# fonte.net
KiCad netlist of a schematic drawn in EAGLE
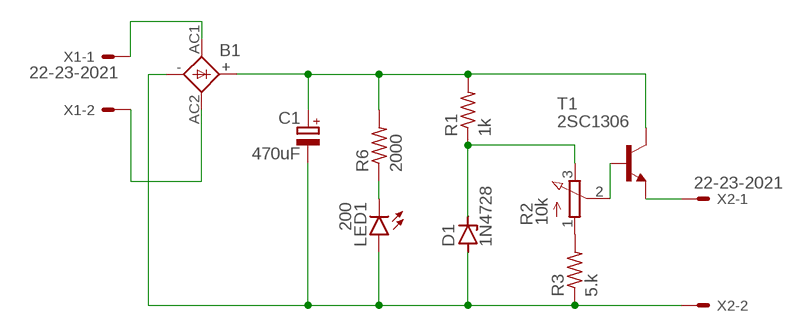
[diagram p0: schematic, sheet 1]

(export (version "E")
  (design (tool "Eeschema 10.0.6"))
  (components
    (comp (ref "B1")
      (value "GBPC1")
      (footprint "eagle-import:GBPC1")
      (libsource (lib "eagle-import") (part "GBPC1"))
    )
    (comp (ref "C1")
      (value "470uF")
      (footprint "eagle-import:B45181B")
      (libsource (lib "eagle-import") (part "CPOL-EUB45181B"))
    )
    (comp (ref "D1")
      (value "1N4728")
      (footprint "eagle-import:DO41Z10")
      (libsource (lib "eagle-import") (part "1N4728"))
    )
    (comp (ref "LED1")
      (value "200")
      (footprint "eagle-import:LED3MM")
      (libsource (lib "eagle-import") (part "LED3MM"))
    )
    (comp (ref "R1")
      (value "1k")
      (footprint "eagle-import:0204_7")
      (libsource (lib "eagle-import") (part "R-US_0204/7"))
    )
    (comp (ref "R2")
      (value "10k")
      (footprint "eagle-import:3RP_1610N")
      (libsource (lib "eagle-import") (part "3RP/1610N"))
    )
    (comp (ref "R3")
      (value "5.k")
      (footprint "eagle-import:0204_7")
      (libsource (lib "eagle-import") (part "R-US_0204/7"))
    )
    (comp (ref "R6")
      (value "2000")
      (footprint "eagle-import:0204_7")
      (libsource (lib "eagle-import") (part "R-US_0204/7"))
    )
    (comp (ref "T1")
      (value "2SC1306")
      (footprint "eagle-import:TO220BV")
      (libsource (lib "eagle-import") (part "2SC1306"))
    )
    (comp (ref "X1")
      (value "22-23-2021")
      (footprint "eagle-import:22-23-2021")
      (fields (field (name "MF") "MOLEX"))
      (libsource (lib "eagle-import") (part "22-23-2021"))
    )
    (comp (ref "X2")
      (value "22-23-2021")
      (footprint "eagle-import:22-23-2021")
      (fields (field (name "MF") "MOLEX"))
      (libsource (lib "eagle-import") (part "22-23-2021"))
    )
  )
  (nets
    (net (code "1") (name "Net-(LED1-C)") (class "Default")
      (node (ref "LED1") (pin "K") (pinfunction "C_K") (pintype "passive"))
      (node (ref "R6") (pin "1") (pinfunction "1_1") (pintype "passive"))
    )
    (net (code "2") (name "Net-(R2-A)") (class "Default")
      (node (ref "R2") (pin "1") (pinfunction "A_1") (pintype "passive"))
      (node (ref "R3") (pin "2") (pinfunction "2_2") (pintype "passive"))
    )
    (net (code "3") (name "Net-(R2-E)") (class "Default")
      (node (ref "D1") (pin "C") (pinfunction "C_C") (pintype "passive"))
      (node (ref "R1") (pin "1") (pinfunction "1_1") (pintype "passive"))
      (node (ref "R2") (pin "3") (pinfunction "E_3") (pintype "passive"))
    )
    (net (code "4") (name "Net-(R2-S)") (class "Default")
      (node (ref "R2") (pin "2") (pinfunction "S_2") (pintype "passive"))
      (node (ref "T1") (pin "1") (pinfunction "B_1") (pintype "passive"))
    )
    (net (code "5") (name "Net-(T1-C)") (class "Default")
      (node (ref "B1") (pin "+") (pinfunction "+_+") (pintype "passive"))
      (node (ref "C1") (pin "+") (pinfunction "+_+") (pintype "passive"))
      (node (ref "R1") (pin "2") (pinfunction "2_2") (pintype "passive"))
      (node (ref "R6") (pin "2") (pinfunction "2_2") (pintype "passive"))
      (node (ref "T1") (pin "2") (pinfunction "C_2") (pintype "passive"))
    )
    (net (code "6") (name "Net-(T1-E)") (class "Default")
      (node (ref "T1") (pin "3") (pinfunction "E_3") (pintype "passive"))
      (node (ref "X2") (pin "1") (pinfunction "S_1") (pintype "passive"))
    )
    (net (code "7") (name "Net-(X1A-S)") (class "Default")
      (node (ref "B1") (pin "AC1") (pinfunction "AC1_AC1") (pintype "passive"))
      (node (ref "X1") (pin "1") (pinfunction "S_1") (pintype "passive"))
    )
    (net (code "8") (name "Net-(X1B-S)") (class "Default")
      (node (ref "B1") (pin "AC2") (pinfunction "AC2_AC2") (pintype "passive"))
      (node (ref "X1") (pin "2") (pinfunction "S_2") (pintype "passive"))
    )
    (net (code "9") (name "Net-(X2B-S)") (class "Default")
      (node (ref "B1") (pin "-") (pinfunction "-_-") (pintype "passive"))
      (node (ref "C1") (pin "-") (pinfunction "-_-") (pintype "passive"))
      (node (ref "D1") (pin "A") (pinfunction "A_A") (pintype "passive"))
      (node (ref "LED1") (pin "A") (pinfunction "A_A") (pintype "passive"))
      (node (ref "R3") (pin "1") (pinfunction "1_1") (pintype "passive"))
      (node (ref "X2") (pin "2") (pinfunction "S_2") (pintype "passive"))
    )
  )
)
